# Klon.net
KiCad netlist of a schematic drawn in Altium Designer
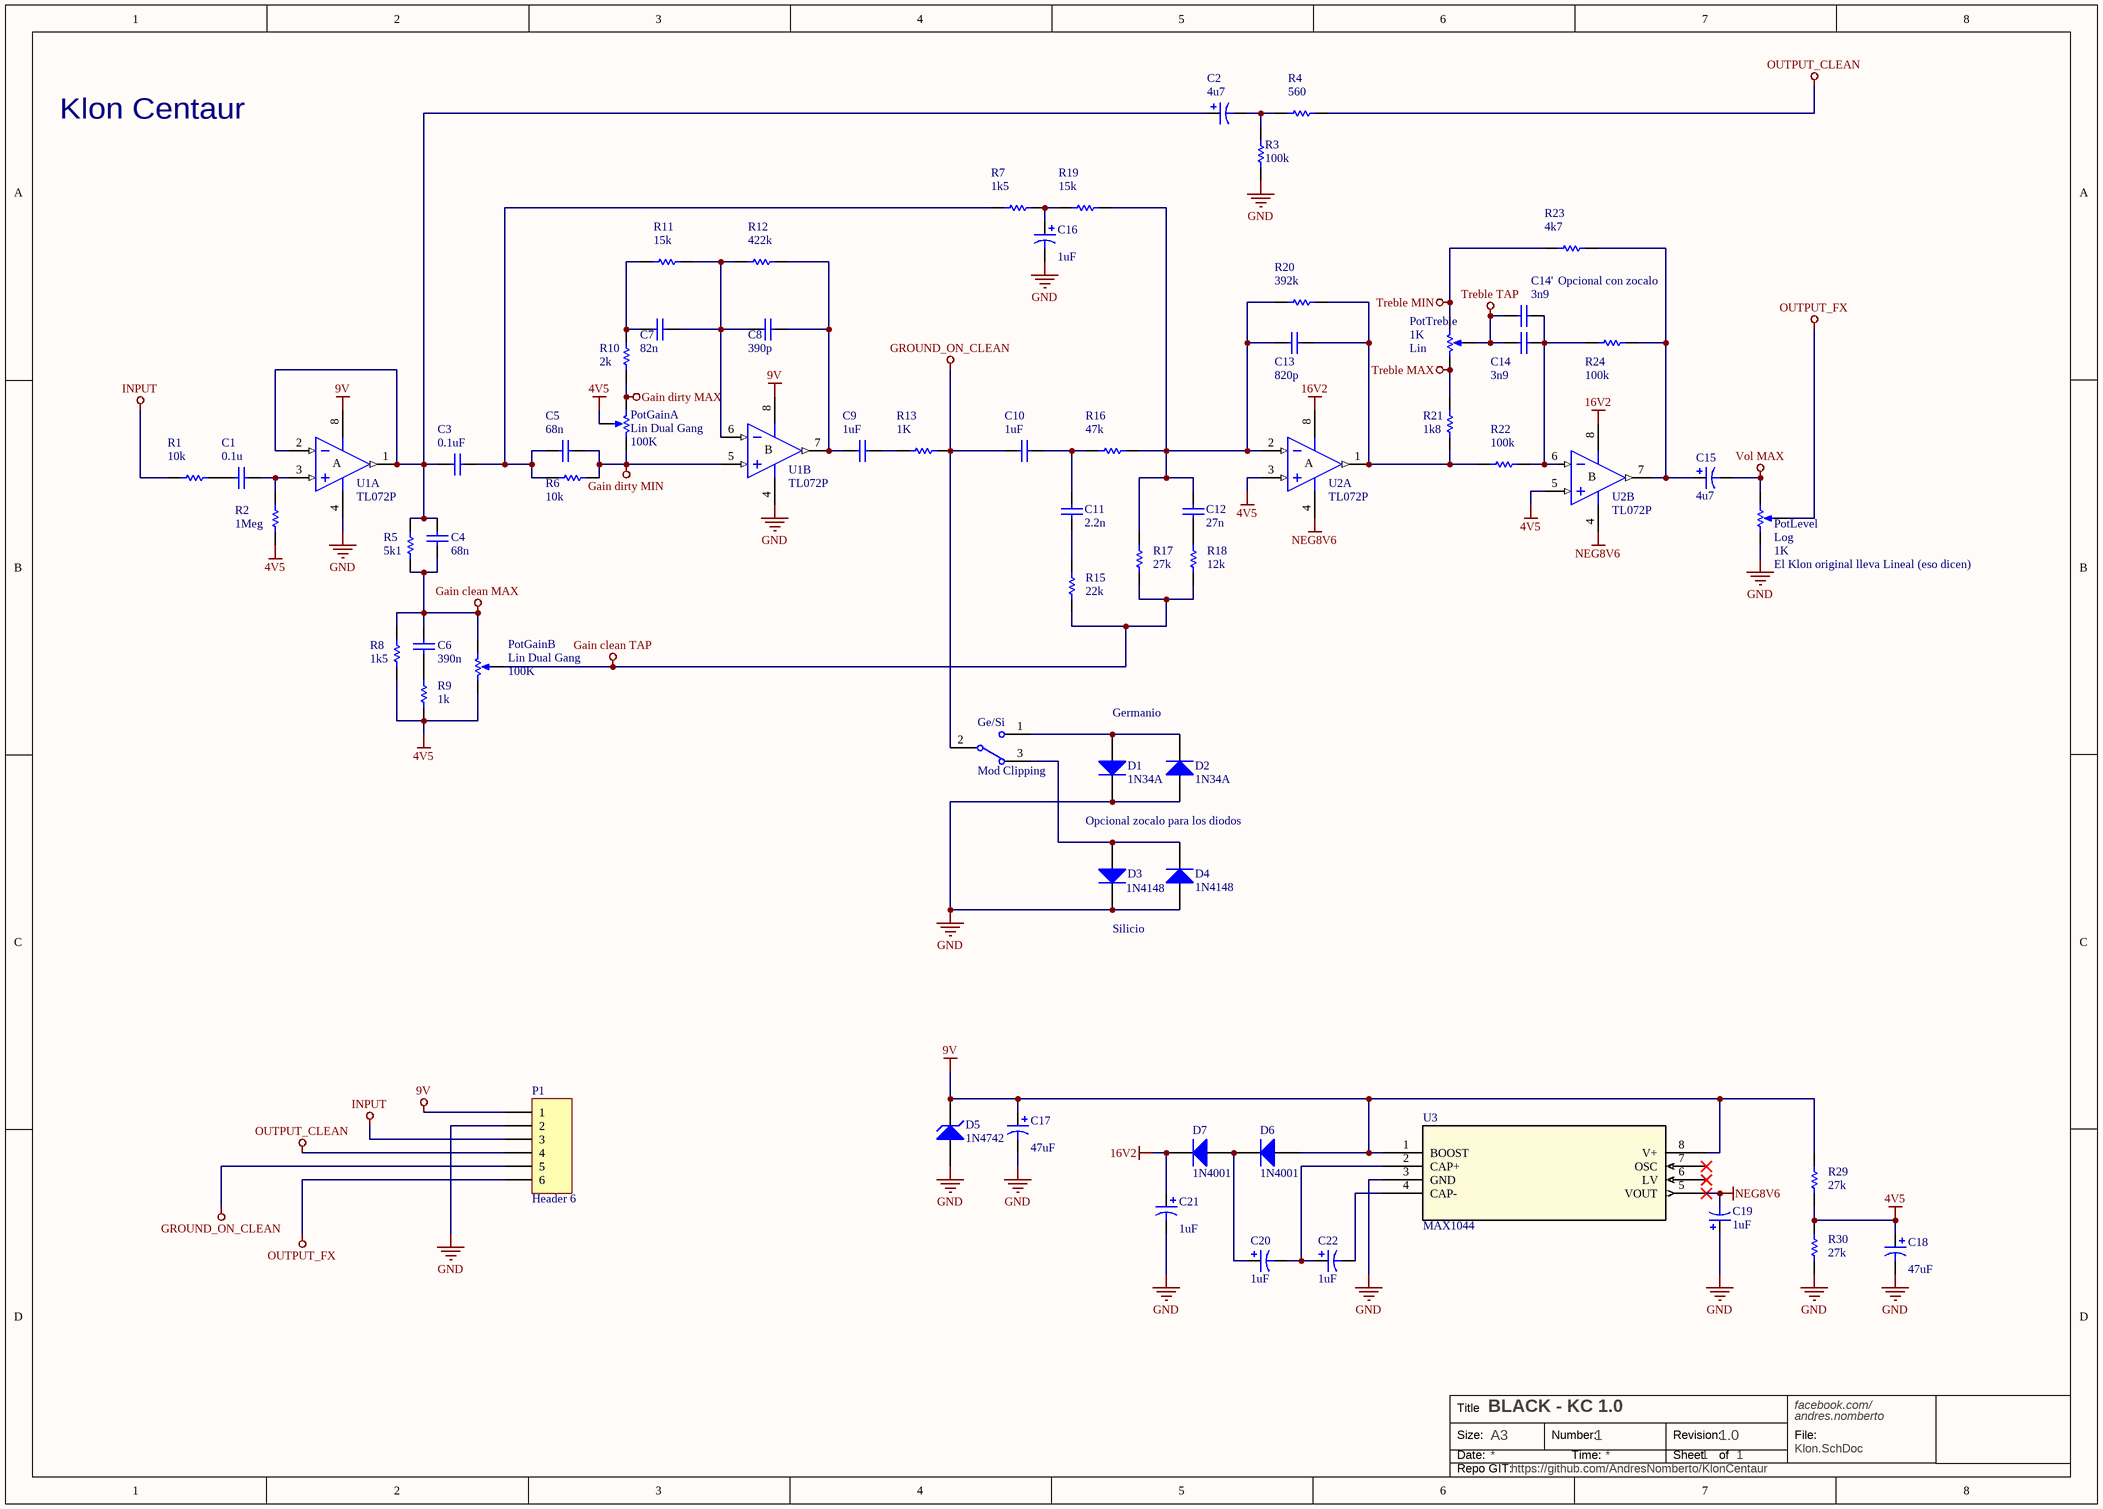
[diagram p0: Klon.SchDoc]

(export (version "E")
  (design (tool "Eeschema 10.0.6"))
  (components
    (comp (ref "C1")
      (value "0.1u")
      (footprint "Cap Box 0.2")
      (description "Film Box")
      (fields (field (name "Comment") "Cap") (field (name "PUBLISHER") "Altium Limited"))
      (libsource (lib "Miscellaneous Devices") (part "Cap"))
    )
    (comp (ref "C2")
      (value "4u7")
      (footprint "Cap Pol 80mil")
      (description "Electrolítico radial")
      (fields (field (name "Comment") "Cap Pol1") (field (name "PUBLISHER") "Altium Limited"))
      (libsource (lib "Miscellaneous Devices") (part "Cap Pol1"))
    )
    (comp (ref "C3")
      (value "0.1uF")
      (footprint "Cap Box 0.2")
      (description "Film Box")
      (fields (field (name "Comment") "Cap") (field (name "PUBLISHER") "Altium Limited"))
      (libsource (lib "Miscellaneous Devices") (part "Cap"))
    )
    (comp (ref "C4")
      (value "68n")
      (footprint "Cap Box 0.2")
      (description "Film Box")
      (fields (field (name "Comment") "Cap") (field (name "PUBLISHER") "Altium Limited"))
      (libsource (lib "Miscellaneous Devices") (part "Cap"))
    )
    (comp (ref "C5")
      (value "68n")
      (footprint "Cap Box 0.2")
      (description "Film Box")
      (fields (field (name "Comment") "Cap") (field (name "PUBLISHER") "Altium Limited"))
      (libsource (lib "Miscellaneous Devices") (part "Cap"))
    )
    (comp (ref "C6")
      (value "390n")
      (footprint "Cap Polyester 200mil")
      (description "Film Box")
      (fields (field (name "Comment") "Cap") (field (name "PUBLISHER") "Altium Limited"))
      (libsource (lib "Miscellaneous Devices") (part "Cap"))
    )
    (comp (ref "C7")
      (value "82n")
      (footprint "Cap Box 0.2")
      (description "Film Box")
      (fields (field (name "Comment") "Cap") (field (name "PUBLISHER") "Altium Limited"))
      (libsource (lib "Miscellaneous Devices") (part "Cap"))
    )
    (comp (ref "C8")
      (value "390p")
      (footprint "Cap Ceramic")
      (description "Cerámico")
      (fields (field (name "Comment") "Cap") (field (name "PUBLISHER") "Altium Limited"))
      (libsource (lib "Miscellaneous Devices") (part "Cap"))
    )
    (comp (ref "C9")
      (value "1uF")
      (footprint "Cap Box 0.2 FAT H400Mil")
      (description "Film Box")
      (fields (field (name "Comment") "Cap") (field (name "PUBLISHER") "Altium Limited"))
      (libsource (lib "Miscellaneous Devices") (part "Cap"))
    )
    (comp (ref "C10")
      (value "1uF")
      (footprint "Cap Box 0.2 FAT H400Mil")
      (description "Film Box")
      (fields (field (name "Comment") "Cap") (field (name "PUBLISHER") "Altium Limited"))
      (libsource (lib "Miscellaneous Devices") (part "Cap"))
    )
    (comp (ref "C11")
      (value "2.2n")
      (footprint "Cap Box 0.2")
      (description "Film Box")
      (fields (field (name "Comment") "Cap") (field (name "PUBLISHER") "Altium Limited"))
      (libsource (lib "Miscellaneous Devices") (part "Cap"))
    )
    (comp (ref "C12")
      (value "27n")
      (footprint "Cap Box 0.2")
      (description "Film Box")
      (fields (field (name "Comment") "Cap") (field (name "PUBLISHER") "Altium Limited"))
      (libsource (lib "Miscellaneous Devices") (part "Cap"))
    )
    (comp (ref "C13")
      (value "820p")
      (footprint "Cap Ceramic Multilayer")
      (description "Cerámico")
      (fields (field (name "Comment") "Cap") (field (name "PUBLISHER") "Altium Limited"))
      (libsource (lib "Miscellaneous Devices") (part "Cap"))
    )
    (comp (ref "C14")
      (value "3n9")
      (footprint "Cap Box 0.2")
      (description "Film Box")
      (fields (field (name "Comment") "Cap") (field (name "PUBLISHER") "Altium Limited"))
      (libsource (lib "Miscellaneous Devices") (part "Cap"))
    )
    (comp (ref "C14'")
      (value "3n9")
      (footprint "Cap Box 0.2 Socket")
      (description "Film Box")
      (fields (field (name "Comment") "Cap") (field (name "PUBLISHER") "Altium Limited"))
      (libsource (lib "Miscellaneous Devices") (part "Cap"))
    )
    (comp (ref "C15")
      (value "4u7")
      (footprint "Cap Pol 80mil")
      (description "Electrolítico radial")
      (fields (field (name "Comment") "Cap Pol1") (field (name "PUBLISHER") "Altium Limited"))
      (libsource (lib "Miscellaneous Devices") (part "Cap Pol1"))
    )
    (comp (ref "C16")
      (value "1uF")
      (footprint "Cap Pol 60mil")
      (description "Electrolítico radial")
      (fields (field (name "Comment") "Cap Pol1") (field (name "PUBLISHER") "Altium Limited"))
      (libsource (lib "Miscellaneous Devices") (part "Cap Pol1"))
    )
    (comp (ref "C17")
      (value "47uF")
      (footprint "Cap Pol 100mil")
      (description "Electrolítico radial")
      (fields (field (name "Comment") "Cap Pol1") (field (name "PUBLISHER") "Altium Limited"))
      (libsource (lib "Miscellaneous Devices") (part "Cap Pol1"))
    )
    (comp (ref "C18")
      (value "47uF")
      (footprint "Cap Pol 100mil")
      (description "Electrolítico radial")
      (fields (field (name "Comment") "Cap Pol1") (field (name "PUBLISHER") "Altium Limited"))
      (libsource (lib "Miscellaneous Devices") (part "Cap Pol1"))
    )
    (comp (ref "C19")
      (value "1uF")
      (footprint "Cap Pol 60mil")
      (description "Electrolítico radial")
      (fields (field (name "Comment") "Cap Pol1") (field (name "PUBLISHER") "Altium Limited"))
      (libsource (lib "Miscellaneous Devices") (part "Cap Pol1"))
    )
    (comp (ref "C20")
      (value "1uF")
      (footprint "Cap Pol 60mil")
      (description "Electrolítico radial")
      (fields (field (name "Comment") "Cap Pol1") (field (name "PUBLISHER") "Altium Limited"))
      (libsource (lib "Miscellaneous Devices") (part "Cap Pol1"))
    )
    (comp (ref "C21")
      (value "1uF")
      (footprint "Cap Pol 60mil")
      (description "Electrolítico radial")
      (fields (field (name "Comment") "Cap Pol1") (field (name "PUBLISHER") "Altium Limited"))
      (libsource (lib "Miscellaneous Devices") (part "Cap Pol1"))
    )
    (comp (ref "C22")
      (value "1uF")
      (footprint "Cap Pol 60mil")
      (description "Electrolítico radial")
      (fields (field (name "Comment") "Cap Pol1") (field (name "PUBLISHER") "Altium Limited"))
      (libsource (lib "Miscellaneous Devices") (part "Cap Pol1"))
    )
    (comp (ref "D1")
      (value "1N34A")
      (footprint "DO35 Germanio")
      (description "Germanio")
      (fields (field (name "PUBLISHER") "Altium Limited"))
      (libsource (lib "Miscellaneous Devices") (part "Diode 1N4148"))
    )
    (comp (ref "D2")
      (value "1N34A")
      (footprint "DO35 Germanio")
      (description "Germanio")
      (fields (field (name "PUBLISHER") "Altium Limited"))
      (libsource (lib "Miscellaneous Devices") (part "Diode 1N4148"))
    )
    (comp (ref "D3")
      (value "1N4148")
      (footprint "DO35")
      (description "Silicio, a gusto")
      (fields (field (name "PUBLISHER") "Altium Limited"))
      (libsource (lib "Miscellaneous Devices") (part "Diode 1N4148"))
    )
    (comp (ref "D4")
      (value "1N4148")
      (footprint "PcbLib1:DO35")
      (description "Silicio, a gusto")
      (fields (field (name "PUBLISHER") "Altium Limited"))
      (libsource (lib "Miscellaneous Devices") (part "Diode 1N4148"))
    )
    (comp (ref "D5")
      (value "1N4742")
      (footprint "DO41 Zener 250mils")
      (description "Zener Diode")
      (fields (field (name "PUBLISHER") "Altium Limited"))
      (libsource (lib "Miscellaneous Devices") (part "D Zener"))
    )
    (comp (ref "D6")
      (value "1N4001")
      (footprint "DO41")
      (description "Diodo")
      (fields (field (name "PUBLISHER") "Altium Limited"))
      (libsource (lib "Miscellaneous Devices") (part "Diode 1N4001"))
    )
    (comp (ref "D7")
      (value "1N4001")
      (footprint "DO41")
      (description "Diodo")
      (fields (field (name "PUBLISHER") "Altium Limited"))
      (libsource (lib "Miscellaneous Devices") (part "Diode 1N4001"))
    )
    (comp (ref "Ge/Si")
      (value "Mod Clipping")
      (footprint "SWITCH SPDT 5mm")
      (description "SPDT")
      (fields (field (name "PUBLISHER") "Altium Limited"))
      (libsource (lib "Miscellaneous Devices") (part "SW-SPDT"))
    )
    (comp (ref "P1")
      (value "Header 6")
      (footprint "Header 6")
      (description "Conector 6 pines")
      (fields (field (name "PUBLISHER") "Altium Limited"))
      (libsource (lib "Miscellaneous Connectors") (part "Header 6"))
    )
    (comp (ref "PotGain")
      (value "Lin Dual Gang")
      (footprint "POT DUAL")
      (description "Pot Lineal doble")
      (fields (field (name "ALTIUM_VALUE") "100K") (field (name "PUBLISHER") "Altium Limited"))
      (libsource (lib "StompboxesLibs") (part "RPot Dual Gang"))
    )
    (comp (ref "PotLevel")
      (value "Log")
      (footprint "POT")
      (description "Pot Logarítmico (el Klon original usa Lineal)")
      (fields (field (name "ALTIUM_VALUE") "1K") (field (name "PUBLISHER") "Altium Limited"))
      (libsource (lib "StompboxesLibs") (part "RPot"))
    )
    (comp (ref "PotTreble")
      (value "Lin")
      (footprint "POT")
      (description "Pot Lineal")
      (fields (field (name "ALTIUM_VALUE") "1K") (field (name "PUBLISHER") "Altium Limited"))
      (libsource (lib "StompboxesLibs") (part "RPot"))
    )
    (comp (ref "R1")
      (value "10k")
      (footprint "Res 0.2")
      (description "Res 1/8")
      (fields (field (name "Comment") "Res1") (field (name "PUBLISHER") "Altium Limited"))
      (libsource (lib "Miscellaneous Devices") (part "Res1"))
    )
    (comp (ref "R2")
      (value "1Meg")
      (footprint "Res 0.2")
      (description "Res 1/8")
      (fields (field (name "Comment") "Res1") (field (name "PUBLISHER") "Altium Limited"))
      (libsource (lib "Miscellaneous Devices") (part "Res1"))
    )
    (comp (ref "R3")
      (value "100k")
      (footprint "Res 0.2")
      (description "Res 1/8")
      (fields (field (name "Comment") "Res1") (field (name "PUBLISHER") "Altium Limited"))
      (libsource (lib "Miscellaneous Devices") (part "Res1"))
    )
    (comp (ref "R4")
      (value "560")
      (footprint "Res 0.2")
      (description "Res 1/8")
      (fields (field (name "Comment") "Res1") (field (name "PUBLISHER") "Altium Limited"))
      (libsource (lib "Miscellaneous Devices") (part "Res1"))
    )
    (comp (ref "R5")
      (value "5k1")
      (footprint "Res 0.2")
      (description "Res 1/8")
      (fields (field (name "Comment") "Res1") (field (name "PUBLISHER") "Altium Limited"))
      (libsource (lib "Miscellaneous Devices") (part "Res1"))
    )
    (comp (ref "R6")
      (value "10k")
      (footprint "Res 0.2")
      (description "Res 1/8")
      (fields (field (name "Comment") "Res1") (field (name "PUBLISHER") "Altium Limited"))
      (libsource (lib "Miscellaneous Devices") (part "Res1"))
    )
    (comp (ref "R7")
      (value "1k5")
      (footprint "Res 0.2")
      (description "Res 1/8")
      (fields (field (name "Comment") "Res1") (field (name "PUBLISHER") "Altium Limited"))
      (libsource (lib "Miscellaneous Devices") (part "Res1"))
    )
    (comp (ref "R8")
      (value "1k5")
      (footprint "Res 0.2")
      (description "Res 1/8")
      (fields (field (name "Comment") "Res1") (field (name "PUBLISHER") "Altium Limited"))
      (libsource (lib "Miscellaneous Devices") (part "Res1"))
    )
    (comp (ref "R9")
      (value "1k")
      (footprint "Res 0.2")
      (description "Res 1/8")
      (fields (field (name "Comment") "Res1") (field (name "PUBLISHER") "Altium Limited"))
      (libsource (lib "Miscellaneous Devices") (part "Res1"))
    )
    (comp (ref "R10")
      (value "2k")
      (footprint "Res 0.2")
      (description "Res 1/8")
      (fields (field (name "Comment") "Res1") (field (name "PUBLISHER") "Altium Limited"))
      (libsource (lib "Miscellaneous Devices") (part "Res1"))
    )
    (comp (ref "R11")
      (value "15k")
      (footprint "Res 0.2")
      (description "Res 1/8")
      (fields (field (name "Comment") "Res1") (field (name "PUBLISHER") "Altium Limited"))
      (libsource (lib "Miscellaneous Devices") (part "Res1"))
    )
    (comp (ref "R12")
      (value "422k")
      (footprint "Res 0.3")
      (description "Res 1/8 o 1/4")
      (fields (field (name "Comment") "Res1") (field (name "PUBLISHER") "Altium Limited"))
      (libsource (lib "Miscellaneous Devices") (part "Res1"))
    )
    (comp (ref "R13")
      (value "1K")
      (footprint "Res 0.2")
      (description "Res 1/8")
      (fields (field (name "Comment") "Res1") (field (name "PUBLISHER") "Altium Limited"))
      (libsource (lib "Miscellaneous Devices") (part "Res1"))
    )
    (comp (ref "R15")
      (value "22k")
      (footprint "Res 0.2")
      (description "Res 1/8")
      (fields (field (name "Comment") "Res1") (field (name "PUBLISHER") "Altium Limited"))
      (libsource (lib "Miscellaneous Devices") (part "Res1"))
    )
    (comp (ref "R16")
      (value "47k")
      (footprint "Res 0.2")
      (description "Res 1/8")
      (fields (field (name "Comment") "Res1") (field (name "PUBLISHER") "Altium Limited"))
      (libsource (lib "Miscellaneous Devices") (part "Res1"))
    )
    (comp (ref "R17")
      (value "27k")
      (footprint "Res 0.2")
      (description "Res 1/8")
      (fields (field (name "Comment") "Res1") (field (name "PUBLISHER") "Altium Limited"))
      (libsource (lib "Miscellaneous Devices") (part "Res1"))
    )
    (comp (ref "R18")
      (value "12k")
      (footprint "Res 0.2")
      (description "Res 1/8")
      (fields (field (name "Comment") "Res1") (field (name "PUBLISHER") "Altium Limited"))
      (libsource (lib "Miscellaneous Devices") (part "Res1"))
    )
    (comp (ref "R19")
      (value "15k")
      (footprint "Res 0.2")
      (description "Res 1/8")
      (fields (field (name "Comment") "Res1") (field (name "PUBLISHER") "Altium Limited"))
      (libsource (lib "Miscellaneous Devices") (part "Res1"))
    )
    (comp (ref "R20")
      (value "392k")
      (footprint "Res 0.3")
      (description "Res 1/8 o 1/4")
      (fields (field (name "Comment") "Res1") (field (name "PUBLISHER") "Altium Limited"))
      (libsource (lib "Miscellaneous Devices") (part "Res1"))
    )
    (comp (ref "R21")
      (value "1k8")
      (footprint "Res 0.2")
      (description "Res 1/8")
      (fields (field (name "Comment") "Res1") (field (name "PUBLISHER") "Altium Limited"))
      (libsource (lib "Miscellaneous Devices") (part "Res1"))
    )
    (comp (ref "R22")
      (value "100k")
      (footprint "Res 0.2")
      (description "Res 1/8")
      (fields (field (name "Comment") "Res1") (field (name "PUBLISHER") "Altium Limited"))
      (libsource (lib "Miscellaneous Devices") (part "Res1"))
    )
    (comp (ref "R23")
      (value "4k7")
      (footprint "Res 0.2")
      (description "Res 1/8")
      (fields (field (name "Comment") "Res1") (field (name "PUBLISHER") "Altium Limited"))
      (libsource (lib "Miscellaneous Devices") (part "Res1"))
    )
    (comp (ref "R24")
      (value "100k")
      (footprint "Res 0.2")
      (description "Res 1/8")
      (fields (field (name "Comment") "Res1") (field (name "PUBLISHER") "Altium Limited"))
      (libsource (lib "Miscellaneous Devices") (part "Res1"))
    )
    (comp (ref "R29")
      (value "27k")
      (footprint "Res 0.2")
      (description "Res 1/8")
      (fields (field (name "Comment") "Res1") (field (name "PUBLISHER") "Altium Limited"))
      (libsource (lib "Miscellaneous Devices") (part "Res1"))
    )
    (comp (ref "R30")
      (value "27k")
      (footprint "Res 0.2")
      (description "Res 1/8")
      (fields (field (name "Comment") "Res1") (field (name "PUBLISHER") "Altium Limited"))
      (libsource (lib "Miscellaneous Devices") (part "Res1"))
    )
    (comp (ref "U1")
      (value "TL072P")
      (footprint "DIP8")
      (description "Low-Noise JFET-Input Operational Amplifier")
      (fields (field (name "PUBLISHER") "Altium Limited"))
      (libsource (lib "TI Operational Amplifier") (part "TL072P"))
    )
    (comp (ref "U2")
      (value "TL072P")
      (footprint "DIP8")
      (description "Low-Noise JFET-Input Operational Amplifier")
      (fields (field (name "PUBLISHER") "Altium Limited"))
      (libsource (lib "TI Operational Amplifier") (part "TL072P"))
    )
    (comp (ref "U3")
      (value "MAX1044")
      (footprint "DIP8")
      (description "No Description Available")
      (fields
        (field (name "MANUFACTURER_PART_NUMBER") "max1044epa+")
        (field (name "COPYRIGHT") "Copyright (C) 2018 Accelerated Designs. All rights reserved")
      )
      (libsource (lib "2019-08-14_22-06-44") (part "max1044epa+"))
    )
  )
  (nets
    (net (code "1") (name "4V5") (class "Default")
      (node (ref "C18") (pin "1") (pinfunction "1_1") (pintype "passive"))
      (node (ref "PotGain") (pin "2") (pinfunction "TAP_2") (pintype "passive"))
      (node (ref "PotGain") (pin "6") (pinfunction "TOP_6") (pintype "passive"))
      (node (ref "R2") (pin "1") (pinfunction "1_1") (pintype "passive"))
      (node (ref "R29") (pin "1") (pinfunction "1_1") (pintype "passive"))
      (node (ref "R30") (pin "2") (pinfunction "2_2") (pintype "passive"))
      (node (ref "R8") (pin "1") (pinfunction "1_1") (pintype "passive"))
      (node (ref "R9") (pin "1") (pinfunction "1_1") (pintype "passive"))
      (node (ref "U2") (pin "3") (pinfunction "IN+_3") (pintype "input"))
      (node (ref "U2") (pin "5") (pinfunction "IN+_5") (pintype "input"))
    )
    (net (code "2") (name "9V") (class "Default")
      (node (ref "C17") (pin "1") (pinfunction "1_1") (pintype "passive"))
      (node (ref "D5") (pin "2") (pinfunction "K_2") (pintype "passive"))
      (node (ref "D6") (pin "1") (pinfunction "A_1") (pintype "passive"))
      (node (ref "P1") (pin "1") (pinfunction "1_1") (pintype "passive"))
      (node (ref "R29") (pin "2") (pinfunction "2_2") (pintype "passive"))
      (node (ref "U1") (pin "8") (pinfunction "V+_8") (pintype "power_in"))
      (node (ref "U3") (pin "1") (pinfunction "BOOST_1") (pintype "passive"))
      (node (ref "U3") (pin "8") (pinfunction "V+_8") (pintype "power_in"))
    )
    (net (code "3") (name "16V2") (class "Default")
      (node (ref "C21") (pin "1") (pinfunction "1_1") (pintype "passive"))
      (node (ref "D7") (pin "2") (pinfunction "K_2") (pintype "passive"))
      (node (ref "U2") (pin "8") (pinfunction "V+_8") (pintype "power_in"))
    )
    (net (code "4") (name "GND") (class "Default")
      (node (ref "C16") (pin "2") (pinfunction "2_2") (pintype "passive"))
      (node (ref "C17") (pin "2") (pinfunction "2_2") (pintype "passive"))
      (node (ref "C18") (pin "2") (pinfunction "2_2") (pintype "passive"))
      (node (ref "C19") (pin "1") (pinfunction "1_1") (pintype "passive"))
      (node (ref "C21") (pin "2") (pinfunction "2_2") (pintype "passive"))
      (node (ref "D1") (pin "2") (pinfunction "K_2") (pintype "passive"))
      (node (ref "D2") (pin "1") (pinfunction "A_1") (pintype "passive"))
      (node (ref "D3") (pin "2") (pinfunction "K_2") (pintype "passive"))
      (node (ref "D4") (pin "1") (pinfunction "A_1") (pintype "passive"))
      (node (ref "D5") (pin "1") (pinfunction "A_1") (pintype "passive"))
      (node (ref "P1") (pin "2") (pinfunction "2_2") (pintype "passive"))
      (node (ref "PotLevel") (pin "1") (pinfunction "BOT_1") (pintype "passive"))
      (node (ref "R3") (pin "1") (pinfunction "1_1") (pintype "passive"))
      (node (ref "R30") (pin "1") (pinfunction "1_1") (pintype "passive"))
      (node (ref "U1") (pin "4") (pinfunction "V-_4") (pintype "power_in"))
      (node (ref "U3") (pin "3") (pinfunction "GND_3") (pintype "power_in"))
    )
    (net (code "5") (name "GROUND_ON_CLEAN") (class "Default")
      (node (ref "C10") (pin "1") (pinfunction "1_1") (pintype "passive"))
      (node (ref "Ge/Si") (pin "2") (pinfunction "2_2") (pintype "passive"))
      (node (ref "P1") (pin "5") (pinfunction "5_5") (pintype "passive"))
      (node (ref "R13") (pin "2") (pinfunction "2_2") (pintype "passive"))
    )
    (net (code "6") (name "Gain clean MAX") (class "Default")
      (node (ref "C4") (pin "1") (pinfunction "1_1") (pintype "passive"))
      (node (ref "C6") (pin "2") (pinfunction "2_2") (pintype "passive"))
      (node (ref "PotGain") (pin "4") (pinfunction "BOT_4") (pintype "passive"))
      (node (ref "R5") (pin "1") (pinfunction "1_1") (pintype "passive"))
      (node (ref "R8") (pin "2") (pinfunction "2_2") (pintype "passive"))
    )
    (net (code "7") (name "Gain clean TAP") (class "Default")
      (node (ref "PotGain") (pin "5") (pinfunction "TAP_5") (pintype "passive"))
      (node (ref "R15") (pin "1") (pinfunction "1_1") (pintype "passive"))
      (node (ref "R17") (pin "1") (pinfunction "1_1") (pintype "passive"))
      (node (ref "R18") (pin "1") (pinfunction "1_1") (pintype "passive"))
    )
    (net (code "8") (name "Gain dirty MAX") (class "Default")
      (node (ref "PotGain") (pin "3") (pinfunction "TOP_3") (pintype "passive"))
      (node (ref "R10") (pin "1") (pinfunction "1_1") (pintype "passive"))
    )
    (net (code "9") (name "Gain dirty MIN") (class "Default")
      (node (ref "C5") (pin "1") (pinfunction "1_1") (pintype "passive"))
      (node (ref "PotGain") (pin "1") (pinfunction "BOT_1") (pintype "passive"))
      (node (ref "R6") (pin "1") (pinfunction "1_1") (pintype "passive"))
      (node (ref "U1") (pin "5") (pinfunction "IN+_5") (pintype "input"))
    )
    (net (code "10") (name "INPUT") (class "Default")
      (node (ref "P1") (pin "3") (pinfunction "3_3") (pintype "passive"))
      (node (ref "R1") (pin "1") (pinfunction "1_1") (pintype "passive"))
    )
    (net (code "11") (name "NEG8V6") (class "Default")
      (node (ref "C19") (pin "2") (pinfunction "2_2") (pintype "passive"))
      (node (ref "U2") (pin "4") (pinfunction "V-_4") (pintype "power_in"))
      (node (ref "U3") (pin "5") (pinfunction "VOUT_5") (pintype "output"))
    )
    (net (code "12") (name "Net-(C1-Pad1)") (class "Default")
      (node (ref "C1") (pin "1") (pinfunction "1_1") (pintype "passive"))
      (node (ref "R1") (pin "2") (pinfunction "2_2") (pintype "passive"))
    )
    (net (code "13") (name "Net-(C2-Pad2)") (class "Default")
      (node (ref "C2") (pin "2") (pinfunction "2_2") (pintype "passive"))
      (node (ref "R3") (pin "2") (pinfunction "2_2") (pintype "passive"))
      (node (ref "R4") (pin "2") (pinfunction "2_2") (pintype "passive"))
    )
    (net (code "14") (name "Net-(C3-Pad2)") (class "Default")
      (node (ref "C3") (pin "2") (pinfunction "2_2") (pintype "passive"))
      (node (ref "C5") (pin "2") (pinfunction "2_2") (pintype "passive"))
      (node (ref "R6") (pin "2") (pinfunction "2_2") (pintype "passive"))
      (node (ref "R7") (pin "1") (pinfunction "1_1") (pintype "passive"))
    )
    (net (code "15") (name "Net-(C6-Pad1)") (class "Default")
      (node (ref "C6") (pin "1") (pinfunction "1_1") (pintype "passive"))
      (node (ref "R9") (pin "2") (pinfunction "2_2") (pintype "passive"))
    )
    (net (code "16") (name "Net-(C7-Pad1)") (class "Default")
      (node (ref "C7") (pin "1") (pinfunction "1_1") (pintype "passive"))
      (node (ref "R10") (pin "2") (pinfunction "2_2") (pintype "passive"))
      (node (ref "R11") (pin "2") (pinfunction "2_2") (pintype "passive"))
    )
    (net (code "17") (name "Net-(C9-Pad2)") (class "Default")
      (node (ref "C9") (pin "2") (pinfunction "2_2") (pintype "passive"))
      (node (ref "R13") (pin "1") (pinfunction "1_1") (pintype "passive"))
    )
    (net (code "18") (name "Net-(C10-Pad2)") (class "Default")
      (node (ref "C10") (pin "2") (pinfunction "2_2") (pintype "passive"))
      (node (ref "C11") (pin "1") (pinfunction "1_1") (pintype "passive"))
      (node (ref "R16") (pin "2") (pinfunction "2_2") (pintype "passive"))
    )
    (net (code "19") (name "Net-(C11-Pad2)") (class "Default")
      (node (ref "C11") (pin "2") (pinfunction "2_2") (pintype "passive"))
      (node (ref "R15") (pin "2") (pinfunction "2_2") (pintype "passive"))
    )
    (net (code "20") (name "Net-(C12-Pad1)") (class "Default")
      (node (ref "C12") (pin "1") (pinfunction "1_1") (pintype "passive"))
      (node (ref "R18") (pin "2") (pinfunction "2_2") (pintype "passive"))
    )
    (net (code "21") (name "Net-(C16-Pad1)") (class "Default")
      (node (ref "C16") (pin "1") (pinfunction "1_1") (pintype "passive"))
      (node (ref "R19") (pin "1") (pinfunction "1_1") (pintype "passive"))
      (node (ref "R7") (pin "2") (pinfunction "2_2") (pintype "passive"))
    )
    (net (code "22") (name "Net-(D1-A)") (class "Default")
      (node (ref "D1") (pin "1") (pinfunction "A_1") (pintype "passive"))
      (node (ref "D2") (pin "2") (pinfunction "K_2") (pintype "passive"))
      (node (ref "Ge/Si") (pin "1") (pinfunction "1_1") (pintype "passive"))
    )
    (net (code "23") (name "Net-(D3-A)") (class "Default")
      (node (ref "D3") (pin "1") (pinfunction "A_1") (pintype "passive"))
      (node (ref "D4") (pin "2") (pinfunction "K_2") (pintype "passive"))
      (node (ref "Ge/Si") (pin "3") (pinfunction "3_3") (pintype "passive"))
    )
    (net (code "24") (name "Net-(D6-K)") (class "Default")
      (node (ref "C20") (pin "1") (pinfunction "1_1") (pintype "passive"))
      (node (ref "D6") (pin "2") (pinfunction "K_2") (pintype "passive"))
      (node (ref "D7") (pin "1") (pinfunction "A_1") (pintype "passive"))
    )
    (net (code "25") (name "Net-(U1A-IN+)") (class "Default")
      (node (ref "C1") (pin "2") (pinfunction "2_2") (pintype "passive"))
      (node (ref "R2") (pin "2") (pinfunction "2_2") (pintype "passive"))
      (node (ref "U1") (pin "3") (pinfunction "IN+_3") (pintype "input"))
    )
    (net (code "26") (name "Net-(U1A-IN-)") (class "Default")
      (node (ref "C2") (pin "1") (pinfunction "1_1") (pintype "passive"))
      (node (ref "C3") (pin "1") (pinfunction "1_1") (pintype "passive"))
      (node (ref "C4") (pin "2") (pinfunction "2_2") (pintype "passive"))
      (node (ref "R5") (pin "2") (pinfunction "2_2") (pintype "passive"))
      (node (ref "U1") (pin "1") (pinfunction "OUT_1") (pintype "output"))
      (node (ref "U1") (pin "2") (pinfunction "IN-_2") (pintype "input"))
    )
    (net (code "27") (name "Net-(U1B-IN-)") (class "Default")
      (node (ref "C7") (pin "2") (pinfunction "2_2") (pintype "passive"))
      (node (ref "C8") (pin "1") (pinfunction "1_1") (pintype "passive"))
      (node (ref "R11") (pin "1") (pinfunction "1_1") (pintype "passive"))
      (node (ref "R12") (pin "2") (pinfunction "2_2") (pintype "passive"))
      (node (ref "U1") (pin "6") (pinfunction "IN-_6") (pintype "input"))
    )
    (net (code "28") (name "Net-(U1B-OUT)") (class "Default")
      (node (ref "C8") (pin "2") (pinfunction "2_2") (pintype "passive"))
      (node (ref "C9") (pin "1") (pinfunction "1_1") (pintype "passive"))
      (node (ref "R12") (pin "1") (pinfunction "1_1") (pintype "passive"))
      (node (ref "U1") (pin "7") (pinfunction "OUT_7") (pintype "output"))
    )
    (net (code "29") (name "Net-(U2A-IN-)") (class "Default")
      (node (ref "C12") (pin "2") (pinfunction "2_2") (pintype "passive"))
      (node (ref "C13") (pin "2") (pinfunction "2_2") (pintype "passive"))
      (node (ref "R16") (pin "1") (pinfunction "1_1") (pintype "passive"))
      (node (ref "R17") (pin "2") (pinfunction "2_2") (pintype "passive"))
      (node (ref "R19") (pin "2") (pinfunction "2_2") (pintype "passive"))
      (node (ref "R20") (pin "2") (pinfunction "2_2") (pintype "passive"))
      (node (ref "U2") (pin "2") (pinfunction "IN-_2") (pintype "input"))
    )
    (net (code "30") (name "Net-(U2A-OUT)") (class "Default")
      (node (ref "C13") (pin "1") (pinfunction "1_1") (pintype "passive"))
      (node (ref "R20") (pin "1") (pinfunction "1_1") (pintype "passive"))
      (node (ref "R21") (pin "2") (pinfunction "2_2") (pintype "passive"))
      (node (ref "R22") (pin "2") (pinfunction "2_2") (pintype "passive"))
      (node (ref "U2") (pin "1") (pinfunction "OUT_1") (pintype "output"))
    )
    (net (code "31") (name "Net-(U2B-IN-)") (class "Default")
      (node (ref "C14") (pin "1") (pinfunction "1_1") (pintype "passive"))
      (node (ref "C14'") (pin "1") (pinfunction "1_1") (pintype "passive"))
      (node (ref "R22") (pin "1") (pinfunction "1_1") (pintype "passive"))
      (node (ref "R24") (pin "2") (pinfunction "2_2") (pintype "passive"))
      (node (ref "U2") (pin "6") (pinfunction "IN-_6") (pintype "input"))
    )
    (net (code "32") (name "Net-(U2B-OUT)") (class "Default")
      (node (ref "C15") (pin "1") (pinfunction "1_1") (pintype "passive"))
      (node (ref "R23") (pin "1") (pinfunction "1_1") (pintype "passive"))
      (node (ref "R24") (pin "1") (pinfunction "1_1") (pintype "passive"))
      (node (ref "U2") (pin "7") (pinfunction "OUT_7") (pintype "output"))
    )
    (net (code "33") (name "Net-(U3-CAP+)") (class "Default")
      (node (ref "C20") (pin "2") (pinfunction "2_2") (pintype "passive"))
      (node (ref "C22") (pin "1") (pinfunction "1_1") (pintype "passive"))
      (node (ref "U3") (pin "2") (pinfunction "CAP+_2") (pintype "passive"))
    )
    (net (code "34") (name "Net-(U3-CAP-)") (class "Default")
      (node (ref "C22") (pin "2") (pinfunction "2_2") (pintype "passive"))
      (node (ref "U3") (pin "4") (pinfunction "CAP-_4") (pintype "passive"))
    )
    (net (code "35") (name "OUTPUT_CLEAN") (class "Default")
      (node (ref "P1") (pin "4") (pinfunction "4_4") (pintype "passive"))
      (node (ref "R4") (pin "1") (pinfunction "1_1") (pintype "passive"))
    )
    (net (code "36") (name "OUTPUT_FX") (class "Default")
      (node (ref "P1") (pin "6") (pinfunction "6_6") (pintype "passive"))
      (node (ref "PotLevel") (pin "2") (pinfunction "TAP_2") (pintype "passive"))
    )
    (net (code "37") (name "Treble MAX") (class "Default")
      (node (ref "PotTreble") (pin "3") (pinfunction "TOP_3") (pintype "passive"))
      (node (ref "R21") (pin "1") (pinfunction "1_1") (pintype "passive"))
    )
    (net (code "38") (name "Treble MIN") (class "Default")
      (node (ref "PotTreble") (pin "1") (pinfunction "BOT_1") (pintype "passive"))
      (node (ref "R23") (pin "2") (pinfunction "2_2") (pintype "passive"))
    )
    (net (code "39") (name "Treble TAP") (class "Default")
      (node (ref "C14") (pin "2") (pinfunction "2_2") (pintype "passive"))
      (node (ref "C14'") (pin "2") (pinfunction "2_2") (pintype "passive"))
      (node (ref "PotTreble") (pin "2") (pinfunction "TAP_2") (pintype "passive"))
    )
    (net (code "40") (name "Vol MAX") (class "Default")
      (node (ref "C15") (pin "2") (pinfunction "2_2") (pintype "passive"))
      (node (ref "PotLevel") (pin "3") (pinfunction "TOP_3") (pintype "passive"))
    )
    (net (code "41") (name "unconnected-(U3-LV-Pad6)") (class "Default")
      (node (ref "U3") (pin "6") (pinfunction "LV_6") (pintype "input+no_connect"))
    )
    (net (code "42") (name "unconnected-(U3-OSC-Pad7)") (class "Default")
      (node (ref "U3") (pin "7") (pinfunction "OSC_7") (pintype "input+no_connect"))
    )
  )
)
